# Gyrophare-CarteDeCommande.net
KiCad netlist of a schematic drawn in Altium Designer
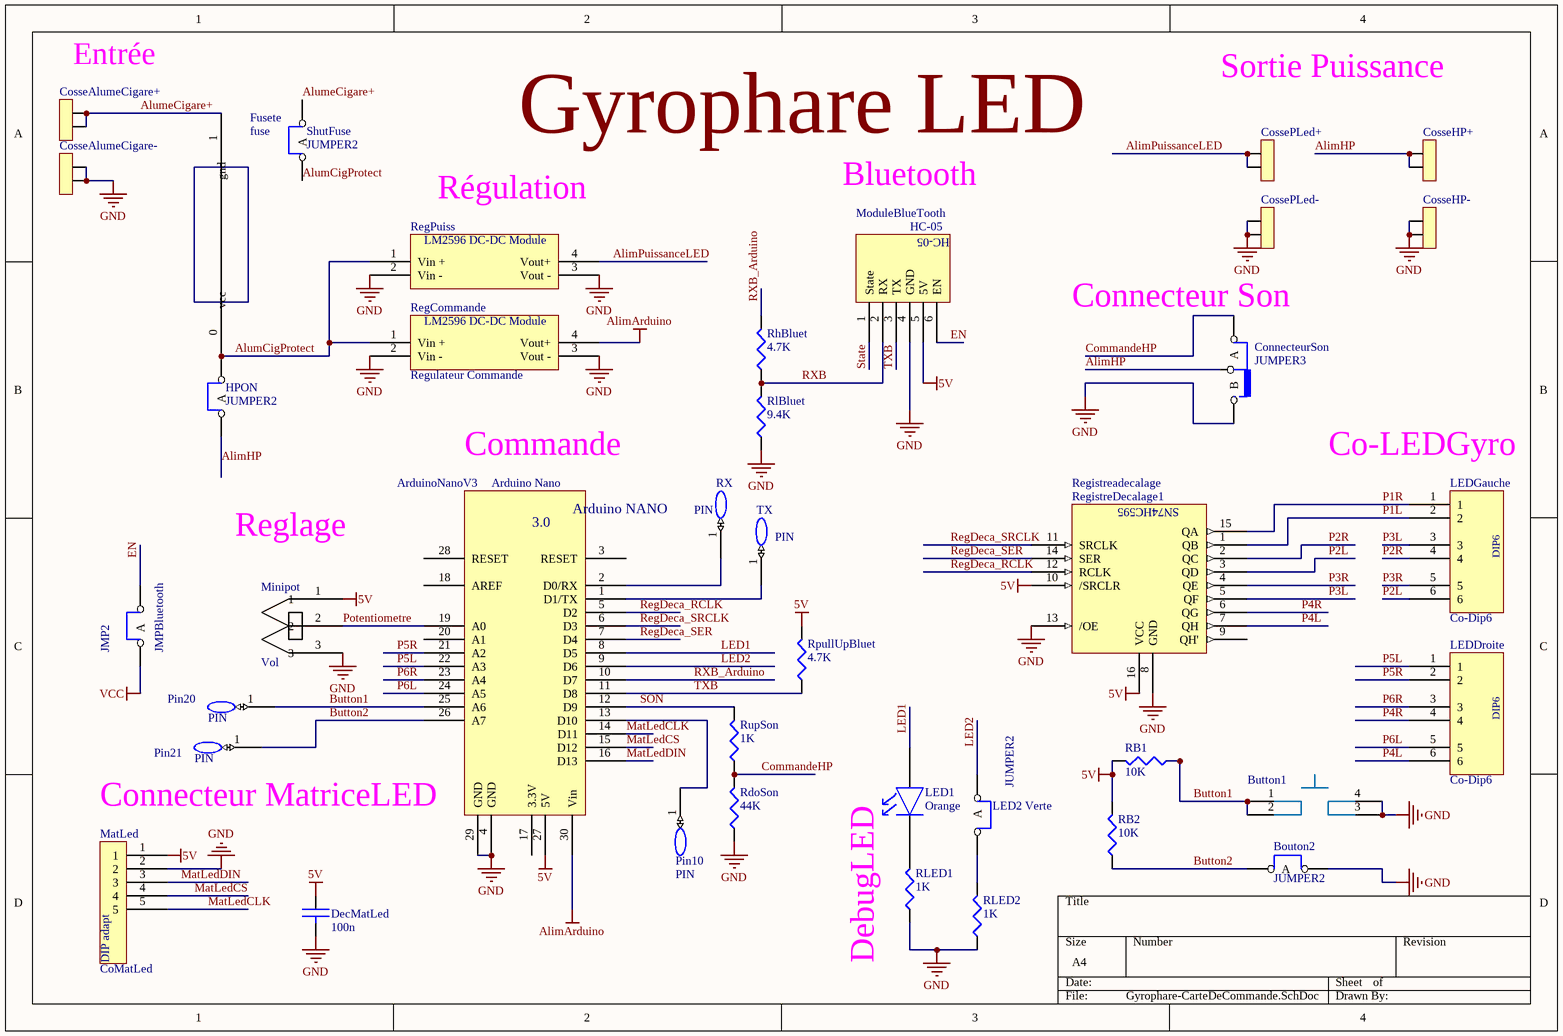
[diagram p0: Gyrophare-CarteDeCommande.SchDoc]

(export (version "E")
  (design (tool "Eeschema 10.0.6"))
  (components
    (comp (ref "ArduinoNanoV3")
      (value "Arduino Nano")
      (footprint "Arduino Nano FootPrint")
      (libsource (lib "Arduino Nano version") (part "Arduino Nano"))
    )
    (comp (ref "Bouton2")
      (value "JUMPER2")
      (footprint "JMP2-100")
      (description "cavalier 1 position")
      (libsource (lib "ISEN_basics") (part "JUMPER2"))
    )
    (comp (ref "Button1")
      (value "SwitchButton")
      (footprint "SwitchMedium")
      (libsource (lib "SwitchButton") (part "SwitchButton"))
    )
    (comp (ref "ConnecteurSon")
      (value "JUMPER3")
      (footprint "JMP3-100")
      (description "cavalier 2 positions")
      (libsource (lib "ISEN_basics_26-05-2015") (part "JUMPER3"))
    )
    (comp (ref "CosseAlumeCigare+")
      (value "CosseAlumeCigare+")
      (footprint "POWER2")
      (description "connecteur alim 2 pôles")
      (libsource (lib "") (part "POWER2_1"))
    )
    (comp (ref "CosseAlumeCigare-")
      (value "CosseAlumeCigare+")
      (footprint "POWER2")
      (description "connecteur alim 2 pôles")
      (libsource (lib "") (part "POWER2_1"))
    )
    (comp (ref "CosseHP+")
      (value "comment")
      (footprint "POWER2")
      (description "connecteur alim 2 pôles")
      (libsource (lib "ISEN_basics") (part "POWER2"))
    )
    (comp (ref "CosseHP-")
      (value "comment")
      (footprint "POWER2")
      (description "connecteur alim 2 pôles")
      (libsource (lib "ISEN_basics") (part "POWER2"))
    )
    (comp (ref "CossePLed+")
      (value "comment")
      (footprint "POWER2")
      (description "connecteur alim 2 pôles")
      (libsource (lib "ISEN_basics") (part "POWER2"))
    )
    (comp (ref "CossePLed-")
      (value "comment")
      (footprint "POWER2")
      (description "connecteur alim 2 pôles")
      (libsource (lib "ISEN_basics") (part "POWER2"))
    )
    (comp (ref "DecMatLed")
      (value "100n")
      (footprint "0805")
      (description "capacité non polarisée")
      (fields (field (name "Comment") "CAP"))
      (libsource (lib "ISEN_basics_26-05-2015") (part "CAP"))
    )
    (comp (ref "Fusete") (value "fuse") (footprint "FUSE") (libsource (lib "fuse") (part "Fuse")))
    (comp (ref "HPON")
      (value "JUMPER2")
      (footprint "JMP2-100")
      (description "cavalier 1 position")
      (libsource (lib "ISEN_basics_26-05-2015") (part "JUMPER2"))
    )
    (comp (ref "JMPBluetooth")
      (value "JMP2")
      (footprint "JMP2-100")
      (description "cavalier 1 position")
      (libsource (lib "ISEN_basics") (part "JUMPER2"))
    )
    (comp (ref "LED1")
      (value "Orange")
      (footprint "LED0805")
      (description "LED 5mm/3mm/CMS")
      (libsource (lib "ISEN_basics_26-05-2015") (part "LED"))
    )
    (comp (ref "LED2 Verte")
      (value "JUMPER2")
      (footprint "JMP2-100")
      (description "cavalier 1 position")
      (libsource (lib "ISEN_basics") (part "JUMPER2"))
    )
    (comp (ref "LEDDroite")
      (value "Co-Dip6")
      (footprint "DIP6")
      (libsource (lib "Co-DoubleDip") (part "Co-Dip6"))
    )
    (comp (ref "LEDGauche")
      (value "Co-Dip6")
      (footprint "DIP6")
      (libsource (lib "Co-DoubleDip") (part "Co-Dip6"))
    )
    (comp (ref "MatLed")
      (value "CoMatLed")
      (footprint "ADAPTATEURDIP5")
      (libsource (lib "AdaptateurDip") (part "DipAdapt5"))
    )
    (comp (ref "Minipot")
      (value "Vol")
      (footprint "MiniTrimer")
      (libsource (lib "MiniTrimmer") (part "MiniPotentiometre"))
    )
    (comp (ref "ModuleBlueTooth")
      (value "HC-05")
      (footprint "HC-05 Droit")
      (libsource (lib "ModuleBluetooth") (part "HC-05"))
    )
    (comp (ref "Pin10") (value "PIN") (footprint "TESTPOINT") (libsource (lib "") (part "PIN_1")))
    (comp (ref "Pin20")
      (value "PIN")
      (footprint "TESTPOINT")
      (libsource (lib "ISEN_basics_26-05-2015") (part "PIN"))
    )
    (comp (ref "Pin21")
      (value "PIN")
      (footprint "TESTPOINT")
      (libsource (lib "ISEN_basics_26-05-2015") (part "PIN"))
    )
    (comp (ref "RB1")
      (value "10K")
      (footprint "0805")
      (description "resistance")
      (fields (field (name "Comment") "RES"))
      (libsource (lib "ISEN_basics_26-05-2015") (part "RES"))
    )
    (comp (ref "RB2")
      (value "10K")
      (footprint "0805")
      (description "resistance")
      (fields (field (name "Comment") "RES"))
      (libsource (lib "ISEN_basics_26-05-2015") (part "RES"))
    )
    (comp (ref "RdoSon")
      (value "44K")
      (footprint "0805")
      (description "resistance")
      (fields (field (name "Comment") "RES"))
      (libsource (lib "ISEN_basics_26-05-2015") (part "RES"))
    )
    (comp (ref "RegCommande")
      (value "Regulateur Commande")
      (footprint "Module LM2596 DC-DC")
      (libsource (lib "Régulateur de Tension LM2596") (part "Component_1"))
    )
    (comp (ref "RegistreDecalage1")
      (value "Registreadecalage")
      (footprint "74HC595")
      (libsource (lib "74HC595") (part "74HC595"))
    )
    (comp (ref "RegPuiss")
      (value "Regulateur Puissant")
      (footprint "Module LM2596 DC-DC")
      (libsource (lib "Régulateur de Tension LM2596") (part "Component_1"))
    )
    (comp (ref "RhBluet")
      (value "4.7K")
      (footprint "0805")
      (description "resistance")
      (fields (field (name "Comment") "RES"))
      (libsource (lib "ISEN_basics") (part "RES"))
    )
    (comp (ref "RlBluet")
      (value "9.4K")
      (footprint "0805")
      (description "resistance")
      (fields (field (name "Comment") "RES"))
      (libsource (lib "ISEN_basics") (part "RES"))
    )
    (comp (ref "RLED1")
      (value "1K")
      (footprint "0805")
      (description "resistance")
      (fields (field (name "Comment") "RES"))
      (libsource (lib "ISEN_basics_26-05-2015") (part "RES"))
    )
    (comp (ref "RLED2")
      (value "1K")
      (footprint "0805")
      (description "resistance")
      (fields (field (name "Comment") "RES"))
      (libsource (lib "ISEN_basics_26-05-2015") (part "RES"))
    )
    (comp (ref "RpullUpBluet")
      (value "4.7K")
      (footprint "0805")
      (description "resistance")
      (fields (field (name "Comment") "RES"))
      (libsource (lib "ISEN_basics") (part "RES"))
    )
    (comp (ref "RupSon")
      (value "1K")
      (footprint "0805")
      (description "resistance")
      (fields (field (name "Comment") "RES"))
      (libsource (lib "ISEN_basics_26-05-2015") (part "RES"))
    )
    (comp (ref "RX") (value "PIN") (footprint "TESTPOINT") (libsource (lib "") (part "PIN_1")))
    (comp (ref "ShutFuse")
      (value "JUMPER2")
      (footprint "JMP2-100")
      (description "cavalier 1 position")
      (libsource (lib "ISEN_basics") (part "JUMPER2"))
    )
    (comp (ref "TX") (value "PIN") (footprint "TESTPOINT") (libsource (lib "") (part "PIN_1")))
  )
  (nets
    (net (code "1") (name "/AlimHP") (class "Default")
      (node (ref "ConnecteurSon") (pin "3") (pinfunction "com_3") (pintype "passive"))
      (node (ref "CosseHP+") (pin "1") (pintype "passive"))
      (node (ref "CosseHP+") (pin "2") (pintype "passive"))
      (node (ref "HPON") (pin "1") (pinfunction "A_1") (pintype "passive"))
    )
    (net (code "2") (name "/AlimPuissanceLED") (class "Default")
      (node (ref "CossePLed+") (pin "1") (pintype "passive"))
      (node (ref "CossePLed+") (pin "2") (pintype "passive"))
      (node (ref "RegPuiss") (pin "4") (pinfunction "Vout+_4") (pintype "passive"))
    )
    (net (code "3") (name "/AlumCigProtect") (class "Default")
      (node (ref "Fusete") (pin "0") (pinfunction "vcc_0") (pintype "passive"))
      (node (ref "HPON") (pin "2") (pinfunction "com_2") (pintype "passive"))
      (node (ref "RegCommande") (pin "1") (pinfunction "Vin_+_1") (pintype "passive"))
      (node (ref "RegPuiss") (pin "1") (pinfunction "Vin_+_1") (pintype "passive"))
      (node (ref "ShutFuse") (pin "1") (pinfunction "A_1") (pintype "passive"))
    )
    (net (code "4") (name "/AlumeCigare+") (class "Default")
      (node (ref "CosseAlumeCigare+") (pin "1") (pintype "passive"))
      (node (ref "CosseAlumeCigare+") (pin "2") (pintype "passive"))
      (node (ref "Fusete") (pin "1") (pinfunction "gnd_1") (pintype "passive"))
      (node (ref "ShutFuse") (pin "2") (pinfunction "com_2") (pintype "passive"))
    )
    (net (code "5") (name "/Button1") (class "Default")
      (node (ref "ArduinoNanoV3") (pin "25") (pinfunction "A6_25") (pintype "passive"))
      (node (ref "Button1") (pin "1") (pinfunction "1_1") (pintype "passive"))
      (node (ref "Button1") (pin "2") (pinfunction "2_2") (pintype "passive"))
      (node (ref "Pin20") (pin "1") (pintype "bidirectional"))
      (node (ref "RB1") (pin "1") (pintype "passive"))
    )
    (net (code "6") (name "/Button2") (class "Default")
      (node (ref "ArduinoNanoV3") (pin "26") (pinfunction "A7_26") (pintype "passive"))
      (node (ref "Bouton2") (pin "1") (pinfunction "A_1") (pintype "passive"))
      (node (ref "Pin21") (pin "1") (pintype "bidirectional"))
      (node (ref "RB2") (pin "1") (pintype "passive"))
    )
    (net (code "7") (name "/CommandeHP") (class "Default")
      (node (ref "ConnecteurSon") (pin "1") (pinfunction "A_1") (pintype "passive"))
      (node (ref "RdoSon") (pin "2") (pintype "passive"))
      (node (ref "RupSon") (pin "1") (pintype "passive"))
    )
    (net (code "8") (name "/EN") (class "Default")
      (node (ref "JMPBluetooth") (pin "2") (pinfunction "com_2") (pintype "passive"))
      (node (ref "ModuleBlueTooth") (pin "6") (pinfunction "EN_6") (pintype "passive"))
    )
    (net (code "9") (name "/LED1") (class "Default")
      (node (ref "ArduinoNanoV3") (pin "8") (pinfunction "D5_8") (pintype "passive"))
      (node (ref "LED1") (pin "A") (pinfunction "8_A") (pintype "passive"))
    )
    (net (code "10") (name "/LED2") (class "Default")
      (node (ref "ArduinoNanoV3") (pin "9") (pinfunction "D6_9") (pintype "passive"))
      (node (ref "LED2 Verte") (pin "1") (pinfunction "A_1") (pintype "passive"))
    )
    (net (code "11") (name "/MatLedCLK") (class "Default")
      (node (ref "ArduinoNanoV3") (pin "14") (pinfunction "D11_14") (pintype "passive"))
      (node (ref "MatLed") (pin "5") (pinfunction "5_5") (pintype "passive"))
    )
    (net (code "12") (name "/MatLedCS") (class "Default")
      (node (ref "ArduinoNanoV3") (pin "15") (pinfunction "D12_15") (pintype "passive"))
      (node (ref "MatLed") (pin "4") (pinfunction "4_4") (pintype "passive"))
    )
    (net (code "13") (name "/MatLedDIN") (class "Default")
      (node (ref "ArduinoNanoV3") (pin "16") (pinfunction "D13_16") (pintype "passive"))
      (node (ref "MatLed") (pin "3") (pinfunction "3_3") (pintype "passive"))
    )
    (net (code "14") (name "/P1L") (class "Default")
      (node (ref "LEDGauche") (pin "2") (pinfunction "2_2") (pintype "passive"))
      (node (ref "RegistreDecalage1") (pin "1") (pinfunction "QB_1") (pintype "output"))
    )
    (net (code "15") (name "/P1R") (class "Default")
      (node (ref "LEDGauche") (pin "1") (pinfunction "1_1") (pintype "passive"))
      (node (ref "RegistreDecalage1") (pin "15") (pinfunction "QA_15") (pintype "output"))
    )
    (net (code "16") (name "/P2L") (class "Default")
      (node (ref "LEDGauche") (pin "6") (pinfunction "6_6") (pintype "passive"))
      (node (ref "RegistreDecalage1") (pin "3") (pinfunction "QD_3") (pintype "output"))
    )
    (net (code "17") (name "/P2R") (class "Default")
      (node (ref "LEDGauche") (pin "4") (pinfunction "4_4") (pintype "passive"))
      (node (ref "RegistreDecalage1") (pin "2") (pinfunction "QC_2") (pintype "output"))
    )
    (net (code "18") (name "/P3L") (class "Default")
      (node (ref "LEDGauche") (pin "3") (pinfunction "3_3") (pintype "passive"))
      (node (ref "RegistreDecalage1") (pin "5") (pinfunction "QF_5") (pintype "output"))
    )
    (net (code "19") (name "/P3R") (class "Default")
      (node (ref "LEDGauche") (pin "5") (pinfunction "5_5") (pintype "passive"))
      (node (ref "RegistreDecalage1") (pin "4") (pinfunction "QE_4") (pintype "output"))
    )
    (net (code "20") (name "/P4L") (class "Default")
      (node (ref "LEDDroite") (pin "6") (pinfunction "6_6") (pintype "passive"))
      (node (ref "RegistreDecalage1") (pin "7") (pinfunction "QH_7") (pintype "output"))
    )
    (net (code "21") (name "/P4R") (class "Default")
      (node (ref "LEDDroite") (pin "4") (pinfunction "4_4") (pintype "passive"))
      (node (ref "RegistreDecalage1") (pin "6") (pinfunction "QG_6") (pintype "output"))
    )
    (net (code "22") (name "/P5L") (class "Default")
      (node (ref "ArduinoNanoV3") (pin "22") (pinfunction "A3_22") (pintype "passive"))
      (node (ref "LEDDroite") (pin "1") (pinfunction "1_1") (pintype "passive"))
    )
    (net (code "23") (name "/P5R") (class "Default")
      (node (ref "ArduinoNanoV3") (pin "21") (pinfunction "A2_21") (pintype "passive"))
      (node (ref "LEDDroite") (pin "2") (pinfunction "2_2") (pintype "passive"))
    )
    (net (code "24") (name "/P6L") (class "Default")
      (node (ref "ArduinoNanoV3") (pin "24") (pinfunction "A5_24") (pintype "passive"))
      (node (ref "LEDDroite") (pin "5") (pinfunction "5_5") (pintype "passive"))
    )
    (net (code "25") (name "/P6R") (class "Default")
      (node (ref "ArduinoNanoV3") (pin "23") (pinfunction "A4_23") (pintype "passive"))
      (node (ref "LEDDroite") (pin "3") (pinfunction "3_3") (pintype "passive"))
    )
    (net (code "26") (name "/Potentiometre") (class "Default")
      (node (ref "ArduinoNanoV3") (pin "19") (pinfunction "A0_19") (pintype "passive"))
      (node (ref "Minipot") (pin "2") (pinfunction "2_2") (pintype "passive"))
    )
    (net (code "27") (name "/RXB") (class "Default")
      (node (ref "ModuleBlueTooth") (pin "2") (pinfunction "RX_2") (pintype "passive"))
      (node (ref "RhBluet") (pin "1") (pintype "passive"))
      (node (ref "RlBluet") (pin "2") (pintype "passive"))
    )
    (net (code "28") (name "/RXB_Arduino") (class "Default")
      (node (ref "ArduinoNanoV3") (pin "10") (pinfunction "D7_10") (pintype "passive"))
      (node (ref "RhBluet") (pin "2") (pintype "passive"))
    )
    (net (code "29") (name "/RegDeca_RCLK") (class "Default")
      (node (ref "ArduinoNanoV3") (pin "5") (pinfunction "D2_5") (pintype "passive"))
      (node (ref "RegistreDecalage1") (pin "12") (pinfunction "RCLK_12") (pintype "input"))
    )
    (net (code "30") (name "/RegDeca_SER") (class "Default")
      (node (ref "ArduinoNanoV3") (pin "7") (pinfunction "D4_7") (pintype "passive"))
      (node (ref "RegistreDecalage1") (pin "14") (pinfunction "SER_14") (pintype "input"))
    )
    (net (code "31") (name "/RegDeca_SRCLK") (class "Default")
      (node (ref "ArduinoNanoV3") (pin "6") (pinfunction "D3_6") (pintype "passive"))
      (node (ref "RegistreDecalage1") (pin "11") (pinfunction "SRCLK_11") (pintype "input"))
    )
    (net (code "32") (name "/SON") (class "Default")
      (node (ref "ArduinoNanoV3") (pin "12") (pinfunction "D9_12") (pintype "passive"))
      (node (ref "RupSon") (pin "2") (pintype "passive"))
    )
    (net (code "33") (name "/State") (class "Default")
      (node (ref "ModuleBlueTooth") (pin "1") (pinfunction "State_1") (pintype "passive"))
    )
    (net (code "34") (name "/TXB") (class "Default")
      (node (ref "ArduinoNanoV3") (pin "11") (pinfunction "D8_11") (pintype "passive"))
      (node (ref "ModuleBlueTooth") (pin "3") (pinfunction "TX_3") (pintype "passive"))
      (node (ref "RpullUpBluet") (pin "1") (pintype "passive"))
    )
    (net (code "35") (name "5V") (class "Default")
      (node (ref "ArduinoNanoV3") (pin "27") (pinfunction "5V_27") (pintype "passive"))
      (node (ref "DecMatLed") (pin "1") (pinfunction "1_1") (pintype "passive"))
      (node (ref "MatLed") (pin "1") (pinfunction "1_1") (pintype "passive"))
      (node (ref "Minipot") (pin "1") (pinfunction "1_1") (pintype "passive"))
      (node (ref "ModuleBlueTooth") (pin "5") (pinfunction "5V_5") (pintype "passive"))
      (node (ref "RB1") (pin "2") (pintype "passive"))
      (node (ref "RB2") (pin "2") (pintype "passive"))
      (node (ref "RegistreDecalage1") (pin "10") (pinfunction "/SRCLR_10") (pintype "input"))
      (node (ref "RegistreDecalage1") (pin "16") (pinfunction "VCC_16") (pintype "passive"))
      (node (ref "RpullUpBluet") (pin "2") (pintype "passive"))
    )
    (net (code "36") (name "AlimArduino") (class "Default")
      (node (ref "ArduinoNanoV3") (pin "30") (pinfunction "Vin_30") (pintype "passive"))
      (node (ref "RegCommande") (pin "4") (pinfunction "Vout+_4") (pintype "passive"))
    )
    (net (code "37") (name "GND") (class "Default")
      (node (ref "ArduinoNanoV3") (pin "29") (pinfunction "GND_29") (pintype "passive"))
      (node (ref "ArduinoNanoV3") (pin "4") (pinfunction "GND_4") (pintype "passive"))
      (node (ref "Bouton2") (pin "2") (pinfunction "com_2") (pintype "passive"))
      (node (ref "Button1") (pin "3") (pinfunction "3_3") (pintype "passive"))
      (node (ref "Button1") (pin "4") (pinfunction "4_4") (pintype "passive"))
      (node (ref "ConnecteurSon") (pin "2") (pinfunction "B_2") (pintype "passive"))
      (node (ref "CosseAlumeCigare-") (pin "1") (pintype "passive"))
      (node (ref "CosseAlumeCigare-") (pin "2") (pintype "passive"))
      (node (ref "CosseHP-") (pin "1") (pintype "passive"))
      (node (ref "CosseHP-") (pin "2") (pintype "passive"))
      (node (ref "CossePLed-") (pin "1") (pintype "passive"))
      (node (ref "CossePLed-") (pin "2") (pintype "passive"))
      (node (ref "DecMatLed") (pin "2") (pinfunction "2_2") (pintype "passive"))
      (node (ref "MatLed") (pin "2") (pinfunction "2_2") (pintype "passive"))
      (node (ref "Minipot") (pin "3") (pinfunction "3_3") (pintype "passive"))
      (node (ref "ModuleBlueTooth") (pin "4") (pinfunction "GND_4") (pintype "passive"))
      (node (ref "RLED1") (pin "1") (pintype "passive"))
      (node (ref "RLED2") (pin "1") (pintype "passive"))
      (node (ref "RdoSon") (pin "1") (pintype "passive"))
      (node (ref "RegCommande") (pin "2") (pinfunction "Vin_-_2") (pintype "passive"))
      (node (ref "RegCommande") (pin "3") (pinfunction "Vout_-_3") (pintype "passive"))
      (node (ref "RegPuiss") (pin "2") (pinfunction "Vin_-_2") (pintype "passive"))
      (node (ref "RegPuiss") (pin "3") (pinfunction "Vout_-_3") (pintype "passive"))
      (node (ref "RegistreDecalage1") (pin "13") (pinfunction "/OE_13") (pintype "input"))
      (node (ref "RegistreDecalage1") (pin "8") (pinfunction "GND_8") (pintype "passive"))
      (node (ref "RlBluet") (pin "1") (pintype "passive"))
    )
    (net (code "38") (name "Net-(ArduinoNanoV3-D0{slash}RX)") (class "Default")
      (node (ref "ArduinoNanoV3") (pin "2") (pinfunction "D0/RX_2") (pintype "passive"))
      (node (ref "RX") (pin "1") (pintype "bidirectional"))
    )
    (net (code "39") (name "Net-(ArduinoNanoV3-D1{slash}TX)") (class "Default")
      (node (ref "ArduinoNanoV3") (pin "1") (pinfunction "D1/TX_1") (pintype "passive"))
      (node (ref "TX") (pin "1") (pintype "bidirectional"))
    )
    (net (code "40") (name "Net-(ArduinoNanoV3-D10)") (class "Default")
      (node (ref "ArduinoNanoV3") (pin "13") (pinfunction "D10_13") (pintype "passive"))
      (node (ref "Pin10") (pin "1") (pintype "bidirectional"))
    )
    (net (code "41") (name "Net-(LED1-10)") (class "Default")
      (node (ref "LED1") (pin "K") (pinfunction "10_K") (pintype "passive"))
      (node (ref "RLED1") (pin "2") (pintype "passive"))
    )
    (net (code "42") (name "Net-(LED2 Verte-com)") (class "Default")
      (node (ref "LED2 Verte") (pin "2") (pinfunction "com_2") (pintype "passive"))
      (node (ref "RLED2") (pin "2") (pintype "passive"))
    )
    (net (code "43") (name "VCC") (class "Default")
      (node (ref "JMPBluetooth") (pin "1") (pinfunction "A_1") (pintype "passive"))
    )
    (net (code "44") (name "unconnected-(ArduinoNanoV3-3.3V-Pad17)") (class "Default")
      (node (ref "ArduinoNanoV3") (pin "17") (pinfunction "3.3V_17") (pintype "passive"))
    )
    (net (code "45") (name "unconnected-(ArduinoNanoV3-A1-Pad20)") (class "Default")
      (node (ref "ArduinoNanoV3") (pin "20") (pinfunction "A1_20") (pintype "passive"))
    )
    (net (code "46") (name "unconnected-(ArduinoNanoV3-AREF-Pad18)") (class "Default")
      (node (ref "ArduinoNanoV3") (pin "18") (pinfunction "AREF_18") (pintype "passive"))
    )
    (net (code "47") (name "unconnected-(ArduinoNanoV3-RESET-Pad3)") (class "Default")
      (node (ref "ArduinoNanoV3") (pin "3") (pinfunction "RESET_3") (pintype "passive"))
    )
    (net (code "48") (name "unconnected-(ArduinoNanoV3-RESET-Pad28)") (class "Default")
      (node (ref "ArduinoNanoV3") (pin "28") (pinfunction "RESET_28") (pintype "passive"))
    )
    (net (code "49") (name "unconnected-(RegistreDecalage1-QH'-Pad9)") (class "Default")
      (node (ref "RegistreDecalage1") (pin "9") (pinfunction "QH'_9") (pintype "output"))
    )
  )
)
